# 4_2.net
KiCad netlist of a schematic drawn in Altium Designer
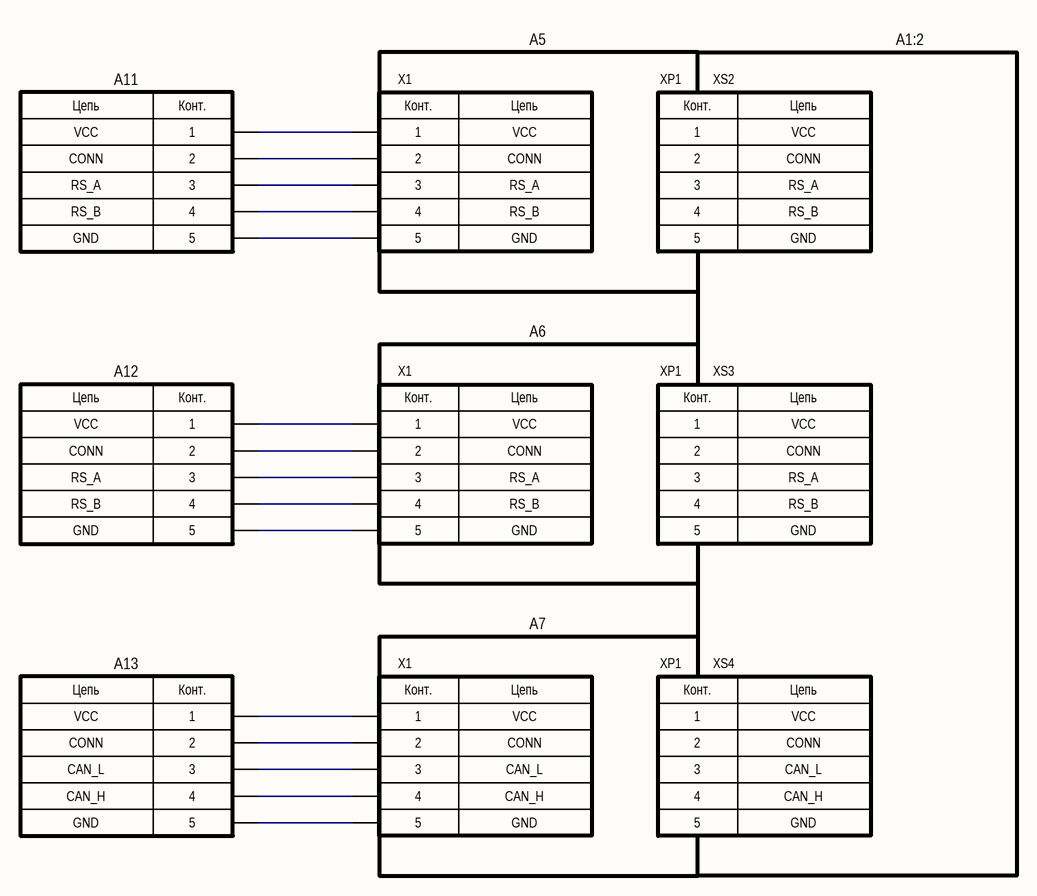
[diagram p0: Э4_2.SchDoc]

(export (version "E")
  (design (tool "Eeschema 10.0.6"))
  (components
    (comp (ref "X1") (value "5pin") (libsource (lib "Schlib1") (part "5pin")))
    (comp (ref "X2") (value "5pin") (libsource (lib "Schlib1") (part "5pin")))
    (comp (ref "X3") (value "5pin_con") (libsource (lib "Schlib1") (part "5pin_con")))
    (comp (ref "X7") (value "5pin") (libsource (lib "Schlib1") (part "5pin")))
    (comp (ref "X8") (value "5pin") (libsource (lib "Schlib1") (part "5pin")))
    (comp (ref "X9") (value "5pin_con") (libsource (lib "Schlib1") (part "5pin_con")))
    (comp (ref "X13") (value "5pin") (libsource (lib "Schlib1") (part "5pin")))
    (comp (ref "X14") (value "5pin") (libsource (lib "Schlib1") (part "5pin")))
    (comp (ref "X15") (value "5pin_con") (libsource (lib "Schlib1") (part "5pin_con")))
  )
  (nets
    (net (code "1") (name "Net-(X1-Pad1)") (class "Default")
      (node (ref "X1") (pin "1") (pinfunction "1_1") (pintype "passive"))
      (node (ref "X2") (pin "1") (pinfunction "1_1") (pintype "passive"))
    )
    (net (code "2") (name "Net-(X1-Pad2)") (class "Default")
      (node (ref "X1") (pin "2") (pinfunction "2_2") (pintype "passive"))
      (node (ref "X2") (pin "2") (pinfunction "2_2") (pintype "passive"))
    )
    (net (code "3") (name "Net-(X1-Pad3)") (class "Default")
      (node (ref "X1") (pin "3") (pinfunction "3_3") (pintype "passive"))
      (node (ref "X2") (pin "3") (pinfunction "3_3") (pintype "passive"))
    )
    (net (code "4") (name "Net-(X1-Pad4)") (class "Default")
      (node (ref "X1") (pin "4") (pinfunction "4_4") (pintype "passive"))
      (node (ref "X2") (pin "4") (pinfunction "4_4") (pintype "passive"))
    )
    (net (code "5") (name "Net-(X1-Pad4)_1") (class "Default")
      (node (ref "X1") (pin "4") (pinfunction "4_4") (pintype "passive"))
      (node (ref "X2") (pin "4") (pinfunction "4_4") (pintype "passive"))
    )
    (net (code "6") (name "Net-(X7-Pad1)") (class "Default")
      (node (ref "X7") (pin "1") (pinfunction "1_1") (pintype "passive"))
      (node (ref "X8") (pin "1") (pinfunction "1_1") (pintype "passive"))
    )
    (net (code "7") (name "Net-(X7-Pad2)") (class "Default")
      (node (ref "X7") (pin "2") (pinfunction "2_2") (pintype "passive"))
      (node (ref "X8") (pin "2") (pinfunction "2_2") (pintype "passive"))
    )
    (net (code "8") (name "Net-(X7-Pad3)") (class "Default")
      (node (ref "X7") (pin "3") (pinfunction "3_3") (pintype "passive"))
      (node (ref "X8") (pin "3") (pinfunction "3_3") (pintype "passive"))
    )
    (net (code "9") (name "Net-(X7-Pad4)") (class "Default")
      (node (ref "X7") (pin "4") (pinfunction "4_4") (pintype "passive"))
      (node (ref "X8") (pin "4") (pinfunction "4_4") (pintype "passive"))
    )
    (net (code "10") (name "Net-(X7-Pad4)_1") (class "Default")
      (node (ref "X7") (pin "4") (pinfunction "4_4") (pintype "passive"))
      (node (ref "X8") (pin "4") (pinfunction "4_4") (pintype "passive"))
    )
    (net (code "11") (name "Net-(X13-Pad1)") (class "Default")
      (node (ref "X13") (pin "1") (pinfunction "1_1") (pintype "passive"))
      (node (ref "X14") (pin "1") (pinfunction "1_1") (pintype "passive"))
    )
    (net (code "12") (name "Net-(X13-Pad2)") (class "Default")
      (node (ref "X13") (pin "2") (pinfunction "2_2") (pintype "passive"))
      (node (ref "X14") (pin "2") (pinfunction "2_2") (pintype "passive"))
    )
    (net (code "13") (name "Net-(X13-Pad3)") (class "Default")
      (node (ref "X13") (pin "3") (pinfunction "3_3") (pintype "passive"))
      (node (ref "X14") (pin "3") (pinfunction "3_3") (pintype "passive"))
    )
    (net (code "14") (name "Net-(X13-Pad4)") (class "Default")
      (node (ref "X13") (pin "4") (pinfunction "4_4") (pintype "passive"))
      (node (ref "X14") (pin "4") (pinfunction "4_4") (pintype "passive"))
    )
    (net (code "15") (name "Net-(X13-Pad4)_1") (class "Default")
      (node (ref "X13") (pin "4") (pinfunction "4_4") (pintype "passive"))
      (node (ref "X14") (pin "4") (pinfunction "4_4") (pintype "passive"))
    )
  )
)
